# Schematic_Small_Unit_Altium.net
KiCad netlist of a schematic drawn in Altium Designer
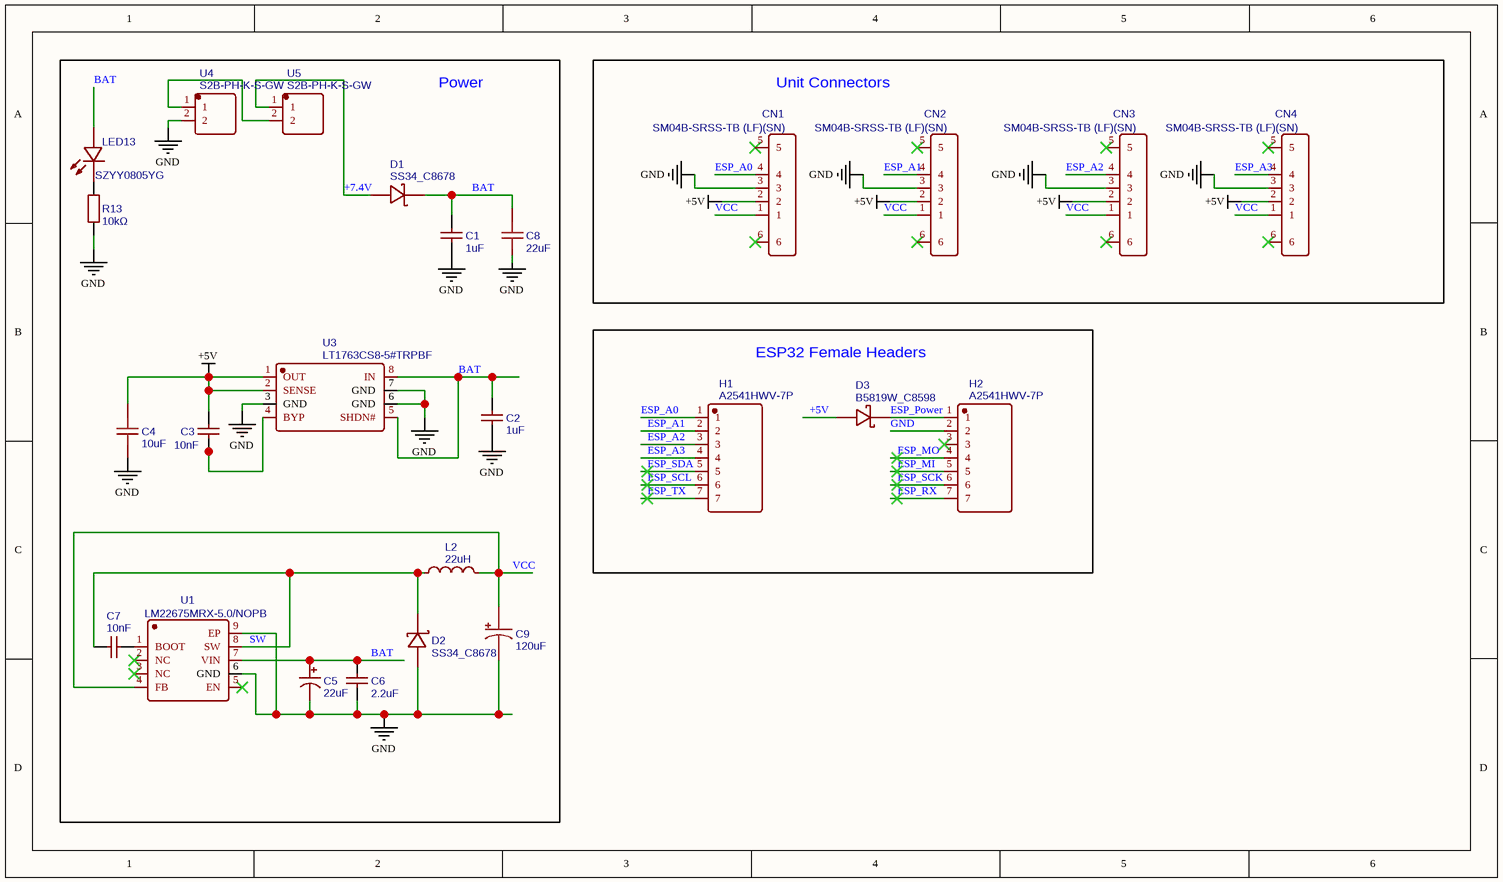
[diagram p0: Schematic_Small_Unit_Altium.schdoc]

(export (version "E")
  (design (tool "Eeschema 10.0.6"))
  (components
    (comp (ref "C1")
      (value "1uF")
      (fields
        (field (name "MANUFACTURER PART") "CL21B105KBFNNNE")
        (field (name "MANUFACTURER") "SAMSUNG(三星)")
      )
      (libsource (lib "altium-import") (part "root_1_1uF_"))
    )
    (comp (ref "C2")
      (value "1uF")
      (fields
        (field (name "MANUFACTURER PART") "CL21B105KBFNNNE")
        (field (name "MANUFACTURER") "SAMSUNG(三星)")
      )
      (libsource (lib "altium-import") (part "root_1_1uF_"))
    )
    (comp (ref "C3")
      (value "10nF")
      (fields
        (field (name "MANUFACTURER PART") "CL05B103KB5NNNC")
        (field (name "MANUFACTURER") "SAMSUNG(三星)")
      )
      (libsource (lib "altium-import") (part "root_1_10nF_"))
    )
    (comp (ref "C4")
      (value "10uF")
      (fields
        (field (name "MANUFACTURER") "SAMSUNG(三星)")
        (field (name "MANUFACTURER PART") "CL10A106KP8NNNC")
      )
      (libsource (lib "altium-import") (part "root_1_10uF_"))
    )
    (comp (ref "C5")
      (value "22uF")
      (fields (field (name "MANUFACTURER") "HONOR(荣誉)") (field (name "MANUFACTURER PART") "RVT1E220M0505"))
      (libsource (lib "altium-import") (part "root_0_22uF_"))
    )
    (comp (ref "C6")
      (value "2.2uF")
      (fields
        (field (name "MANUFACTURER PART") "CL10A225KO8NNNC")
        (field (name "MANUFACTURER") "SAMSUNG(三星)")
      )
      (libsource (lib "altium-import") (part "root_3_2.2uF_"))
    )
    (comp (ref "C7")
      (value "10nF")
      (fields
        (field (name "MANUFACTURER PART") "CL05B103KB5NNNC")
        (field (name "MANUFACTURER") "SAMSUNG(三星)")
      )
      (libsource (lib "altium-import") (part "root_0_10nF_"))
    )
    (comp (ref "C8")
      (value "22uF")
      (fields
        (field (name "MANUFACTURER") "SAMSUNG(三星)")
        (field (name "MANUFACTURER PART") "CL21A226MAYNNNE")
        (field (name "CONTRIBUTOR") "LCSC")
      )
      (libsource (lib "altium-import") (part "root_1_22uF_"))
    )
    (comp (ref "C9")
      (value "120uF")
      (fields
        (field (name "MANUFACTURER") "PANASONIC(松下)")
        (field (name "MANUFACTURER PART") "10SVPC120MV")
        (field (name "CONTRIBUTOR") "LCSC")
      )
      (libsource (lib "altium-import") (part "root_0_120uF_"))
    )
    (comp (ref "CN1")
      (value "SM04B-SRSS-TB (LF)(SN)")
      (fields
        (field (name "MANUFACTURER") "JST")
        (field (name "MANUFACTURER PART") "SM04B-SRSS-TB(LF)(SN)")
        (field (name "CONTRIBUTOR") "LCSC")
      )
      (libsource (lib "altium-import") (part "root_1_SM04B-SRSS-TB (LF)(SN)_"))
    )
    (comp (ref "CN2")
      (value "SM04B-SRSS-TB (LF)(SN)")
      (fields
        (field (name "MANUFACTURER") "JST")
        (field (name "MANUFACTURER PART") "SM04B-SRSS-TB(LF)(SN)")
        (field (name "CONTRIBUTOR") "LCSC")
      )
      (libsource (lib "altium-import") (part "root_1_SM04B-SRSS-TB (LF)(SN)_"))
    )
    (comp (ref "CN3")
      (value "SM04B-SRSS-TB (LF)(SN)")
      (fields
        (field (name "MANUFACTURER") "JST")
        (field (name "MANUFACTURER PART") "SM04B-SRSS-TB(LF)(SN)")
        (field (name "CONTRIBUTOR") "LCSC")
      )
      (libsource (lib "altium-import") (part "root_1_SM04B-SRSS-TB (LF)(SN)_"))
    )
    (comp (ref "CN4")
      (value "SM04B-SRSS-TB (LF)(SN)")
      (fields
        (field (name "MANUFACTURER") "JST")
        (field (name "MANUFACTURER PART") "SM04B-SRSS-TB(LF)(SN)")
        (field (name "CONTRIBUTOR") "LCSC")
      )
      (libsource (lib "altium-import") (part "root_1_SM04B-SRSS-TB (LF)(SN)_"))
    )
    (comp (ref "D1")
      (value "SS34_C8678")
      (fields (field (name "MANUFACTURER PART") "SS34") (field (name "MANUFACTURER") "MDD(辰达半导体)"))
      (libsource (lib "altium-import") (part "root_2_SS34_C8678_"))
    )
    (comp (ref "D2")
      (value "SS34_C8678")
      (fields (field (name "MANUFACTURER PART") "SS34") (field (name "MANUFACTURER") "MDD(辰达半导体)"))
      (libsource (lib "altium-import") (part "root_3_SS34_C8678_"))
    )
    (comp (ref "D3")
      (value "B5819W_C8598")
      (fields (field (name "MANUFACTURER") "CJ(江苏长电/长晶)") (field (name "MANUFACTURER PART") "B5819W SL"))
      (libsource (lib "altium-import") (part "root_2_B5819W_C8598_"))
    )
    (comp (ref "H1")
      (value "A2541HWV-7P")
      (fields (field (name "MANUFACTURER") "CJT(长江连接器)") (field (name "CONTRIBUTOR") "LCSC"))
      (libsource (lib "altium-import") (part "root_0_A2541HWV-7P_"))
    )
    (comp (ref "H2")
      (value "A2541HWV-7P")
      (fields (field (name "MANUFACTURER") "CJT(长江连接器)") (field (name "CONTRIBUTOR") "LCSC"))
      (libsource (lib "altium-import") (part "root_0_A2541HWV-7P_"))
    )
    (comp (ref "L2")
      (value "22uH")
      (fields (field (name "MANUFACTURER") "Sunlord(顺络)") (field (name "MANUFACTURER PART") "SWPA6045S220MT"))
      (libsource (lib "altium-import") (part "root_0_22uH_"))
    )
    (comp (ref "LED13")
      (value "SZYY0805YG")
      (fields (field (name "MANUFACTURER") "yongyu(永裕光电)") (field (name "CONTRIBUTOR") "LCSC"))
      (libsource (lib "altium-import") (part "root_1_SZYY0805YG_"))
    )
    (comp (ref "R13")
      (value "10kΩ")
      (fields
        (field (name "MANUFACTURER") "UNI-ROYAL(厚声)")
        (field (name "MANUFACTURER PART") "0805W8F1002T5E")
      )
      (libsource (lib "altium-import") (part "root_1_10kΩ_"))
    )
    (comp (ref "U1")
      (value "LM22675MRX-5.0/NOPB")
      (fields (field (name "MANUFACTURER") "TI(德州仪器)") (field (name "CONTRIBUTOR") "LCSC"))
      (libsource (lib "altium-import") (part "root_0_LM22675MRX-5.0/NOPB_"))
    )
    (comp (ref "U3")
      (value "LT1763CS8-5#TRPBF")
      (fields (field (name "MANUFACTURER") "ADI(亚德诺)") (field (name "CONTRIBUTOR") "LCSC"))
      (libsource (lib "altium-import") (part "root_0_LT1763CS8-5#TRPBF_"))
    )
    (comp (ref "U4")
      (value "S2B-PH-K-S-GW")
      (fields (field (name "MANUFACTURER") "JST") (field (name "CONTRIBUTOR") "LCSC"))
      (libsource (lib "altium-import") (part "root_0_S2B-PH-K-S-GW_"))
    )
    (comp (ref "U5")
      (value "S2B-PH-K-S-GW")
      (fields (field (name "MANUFACTURER") "JST") (field (name "CONTRIBUTOR") "LCSC"))
      (libsource (lib "altium-import") (part "root_0_S2B-PH-K-S-GW_"))
    )
  )
  (nets
    (net (code "1") (name "+5V") (class "Default")
      (node (ref "C3") (pin "2") (pinfunction "2_2") (pintype "passive"))
      (node (ref "C4") (pin "2") (pinfunction "2_2") (pintype "passive"))
      (node (ref "CN1") (pin "2") (pinfunction "2_2") (pintype "passive"))
      (node (ref "CN2") (pin "2") (pinfunction "2_2") (pintype "passive"))
      (node (ref "CN3") (pin "2") (pinfunction "2_2") (pintype "passive"))
      (node (ref "CN4") (pin "2") (pinfunction "2_2") (pintype "passive"))
      (node (ref "D3") (pin "2") (pinfunction "+_2") (pintype "passive"))
      (node (ref "U3") (pin "1") (pinfunction "OUT_1") (pintype "passive"))
      (node (ref "U3") (pin "2") (pinfunction "SENSE_2") (pintype "passive"))
    )
    (net (code "2") (name "/+7.4V") (class "Default")
      (node (ref "D1") (pin "2") (pinfunction "A_2") (pintype "passive"))
      (node (ref "U5") (pin "1") (pinfunction "1_1") (pintype "passive"))
    )
    (net (code "3") (name "/BAT") (class "Default")
      (node (ref "C1") (pin "2") (pinfunction "2_2") (pintype "passive"))
      (node (ref "C2") (pin "2") (pinfunction "2_2") (pintype "passive"))
      (node (ref "C5") (pin "1") (pinfunction "1_1") (pintype "passive"))
      (node (ref "C6") (pin "1") (pinfunction "1_1") (pintype "passive"))
      (node (ref "C8") (pin "2") (pinfunction "2_2") (pintype "passive"))
      (node (ref "D1") (pin "1") (pinfunction "K_1") (pintype "passive"))
      (node (ref "LED13") (pin "1") (pinfunction "+_1") (pintype "passive"))
      (node (ref "U1") (pin "7") (pinfunction "VIN_7") (pintype "passive"))
      (node (ref "U3") (pin "5") (pinfunction "SHDN#_5") (pintype "passive"))
      (node (ref "U3") (pin "8") (pinfunction "IN_8") (pintype "passive"))
    )
    (net (code "4") (name "/ESP_A0") (class "Default")
      (node (ref "CN1") (pin "4") (pinfunction "4_4") (pintype "passive"))
      (node (ref "H1") (pin "1") (pinfunction "1_1") (pintype "passive"))
    )
    (net (code "5") (name "/ESP_A1") (class "Default")
      (node (ref "CN2") (pin "4") (pinfunction "4_4") (pintype "passive"))
      (node (ref "H1") (pin "2") (pinfunction "2_2") (pintype "passive"))
    )
    (net (code "6") (name "/ESP_A2") (class "Default")
      (node (ref "CN3") (pin "4") (pinfunction "4_4") (pintype "passive"))
      (node (ref "H1") (pin "3") (pinfunction "3_3") (pintype "passive"))
    )
    (net (code "7") (name "/ESP_A3") (class "Default")
      (node (ref "CN4") (pin "4") (pinfunction "4_4") (pintype "passive"))
      (node (ref "H1") (pin "4") (pinfunction "4_4") (pintype "passive"))
    )
    (net (code "10") (name "/ESP_MI") (class "Default")
      (node (ref "H2") (pin "5") (pinfunction "5_5") (pintype "passive"))
    )
    (net (code "16") (name "/ESP_MO") (class "Default")
      (node (ref "H2") (pin "4") (pinfunction "4_4") (pintype "passive"))
    )
    (net (code "17") (name "/ESP_Power") (class "Default")
      (node (ref "D3") (pin "1") (pinfunction "-_1") (pintype "passive"))
      (node (ref "H2") (pin "1") (pinfunction "1_1") (pintype "passive"))
    )
    (net (code "18") (name "/ESP_RX") (class "Default")
      (node (ref "H2") (pin "7") (pinfunction "7_7") (pintype "passive"))
    )
    (net (code "19") (name "/ESP_SCK") (class "Default")
      (node (ref "H2") (pin "6") (pinfunction "6_6") (pintype "passive"))
    )
    (net (code "20") (name "/ESP_SCL") (class "Default")
      (node (ref "H1") (pin "6") (pinfunction "6_6") (pintype "passive"))
    )
    (net (code "21") (name "/ESP_SDA") (class "Default")
      (node (ref "H1") (pin "5") (pinfunction "5_5") (pintype "passive"))
    )
    (net (code "22") (name "/ESP_TX") (class "Default")
      (node (ref "H1") (pin "7") (pinfunction "7_7") (pintype "passive"))
    )
    (net (code "23") (name "/SW") (class "Default")
      (node (ref "C7") (pin "1") (pinfunction "1_1") (pintype "passive"))
      (node (ref "D2") (pin "1") (pinfunction "K_1") (pintype "passive"))
      (node (ref "L2") (pin "1") (pinfunction "1_1") (pintype "passive"))
      (node (ref "U1") (pin "8") (pinfunction "SW_8") (pintype "passive"))
    )
    (net (code "24") (name "/VCC") (class "Default")
      (node (ref "C9") (pin "1") (pinfunction "1_1") (pintype "passive"))
      (node (ref "CN1") (pin "1") (pinfunction "1_1") (pintype "passive"))
      (node (ref "CN2") (pin "1") (pinfunction "1_1") (pintype "passive"))
      (node (ref "CN3") (pin "1") (pinfunction "1_1") (pintype "passive"))
      (node (ref "CN4") (pin "1") (pinfunction "1_1") (pintype "passive"))
      (node (ref "L2") (pin "2") (pinfunction "2_2") (pintype "passive"))
      (node (ref "U1") (pin "4") (pinfunction "FB_4") (pintype "passive"))
    )
    (net (code "25") (name "GND") (class "Default")
      (node (ref "C1") (pin "1") (pinfunction "1_1") (pintype "passive"))
      (node (ref "C2") (pin "1") (pinfunction "1_1") (pintype "passive"))
      (node (ref "C4") (pin "1") (pinfunction "1_1") (pintype "passive"))
      (node (ref "C5") (pin "2") (pinfunction "2_2") (pintype "passive"))
      (node (ref "C6") (pin "2") (pinfunction "2_2") (pintype "passive"))
      (node (ref "C8") (pin "1") (pinfunction "1_1") (pintype "passive"))
      (node (ref "C9") (pin "2") (pinfunction "2_2") (pintype "passive"))
      (node (ref "CN1") (pin "3") (pinfunction "3_3") (pintype "passive"))
      (node (ref "CN2") (pin "3") (pinfunction "3_3") (pintype "passive"))
      (node (ref "CN3") (pin "3") (pinfunction "3_3") (pintype "passive"))
      (node (ref "CN4") (pin "3") (pinfunction "3_3") (pintype "passive"))
      (node (ref "D2") (pin "2") (pinfunction "A_2") (pintype "passive"))
      (node (ref "H2") (pin "2") (pinfunction "2_2") (pintype "passive"))
      (node (ref "R13") (pin "1") (pinfunction "1_1") (pintype "passive"))
      (node (ref "U1") (pin "6") (pinfunction "GND_6") (pintype "passive"))
      (node (ref "U1") (pin "9") (pinfunction "EP_9") (pintype "passive"))
      (node (ref "U3") (pin "3") (pinfunction "GND_3") (pintype "passive"))
      (node (ref "U3") (pin "6") (pinfunction "GND_6") (pintype "passive"))
      (node (ref "U3") (pin "7") (pinfunction "GND_7") (pintype "passive"))
      (node (ref "U4") (pin "2") (pinfunction "2_2") (pintype "passive"))
    )
    (net (code "26") (name "Net-(LED13--)") (class "Default")
      (node (ref "LED13") (pin "2") (pinfunction "-_2") (pintype "passive"))
      (node (ref "R13") (pin "2") (pinfunction "2_2") (pintype "passive"))
    )
    (net (code "27") (name "Net-(U1-BOOT)") (class "Default")
      (node (ref "C7") (pin "2") (pinfunction "2_2") (pintype "passive"))
      (node (ref "U1") (pin "1") (pinfunction "BOOT_1") (pintype "passive"))
    )
    (net (code "28") (name "Net-(U3-BYP)") (class "Default")
      (node (ref "C3") (pin "1") (pinfunction "1_1") (pintype "passive"))
      (node (ref "U3") (pin "4") (pinfunction "BYP_4") (pintype "passive"))
    )
    (net (code "29") (name "Net-(U4-Pad1)") (class "Default")
      (node (ref "U4") (pin "1") (pinfunction "1_1") (pintype "passive"))
      (node (ref "U5") (pin "2") (pinfunction "2_2") (pintype "passive"))
    )
    (net (code "30") (name "unconnected-(CN1-Pad5)") (class "Default")
      (node (ref "CN1") (pin "5") (pinfunction "5_5") (pintype "passive+no_connect"))
    )
    (net (code "31") (name "unconnected-(CN1-Pad6)") (class "Default")
      (node (ref "CN1") (pin "6") (pinfunction "6_6") (pintype "passive+no_connect"))
    )
    (net (code "32") (name "unconnected-(CN2-Pad5)") (class "Default")
      (node (ref "CN2") (pin "5") (pinfunction "5_5") (pintype "passive+no_connect"))
    )
    (net (code "33") (name "unconnected-(CN2-Pad6)") (class "Default")
      (node (ref "CN2") (pin "6") (pinfunction "6_6") (pintype "passive+no_connect"))
    )
    (net (code "34") (name "unconnected-(CN3-Pad5)") (class "Default")
      (node (ref "CN3") (pin "5") (pinfunction "5_5") (pintype "passive+no_connect"))
    )
    (net (code "35") (name "unconnected-(CN3-Pad6)") (class "Default")
      (node (ref "CN3") (pin "6") (pinfunction "6_6") (pintype "passive+no_connect"))
    )
    (net (code "36") (name "unconnected-(CN4-Pad5)") (class "Default")
      (node (ref "CN4") (pin "5") (pinfunction "5_5") (pintype "passive+no_connect"))
    )
    (net (code "37") (name "unconnected-(CN4-Pad6)") (class "Default")
      (node (ref "CN4") (pin "6") (pinfunction "6_6") (pintype "passive+no_connect"))
    )
    (net (code "38") (name "unconnected-(H2-Pad3)") (class "Default")
      (node (ref "H2") (pin "3") (pinfunction "3_3") (pintype "passive+no_connect"))
    )
    (net (code "39") (name "unconnected-(U1-EN-Pad5)") (class "Default")
      (node (ref "U1") (pin "5") (pinfunction "EN_5") (pintype "passive+no_connect"))
    )
    (net (code "40") (name "unconnected-(U1-NC-Pad2)") (class "Default")
      (node (ref "U1") (pin "2") (pinfunction "NC_2") (pintype "passive+no_connect"))
    )
    (net (code "41") (name "unconnected-(U1-NC-Pad3)") (class "Default")
      (node (ref "U1") (pin "3") (pinfunction "NC_3") (pintype "passive+no_connect"))
    )
  )
)
